# FULLMONI-WIDE_IF-Board1_SCH.net
KiCad netlist of a schematic drawn in EAGLE
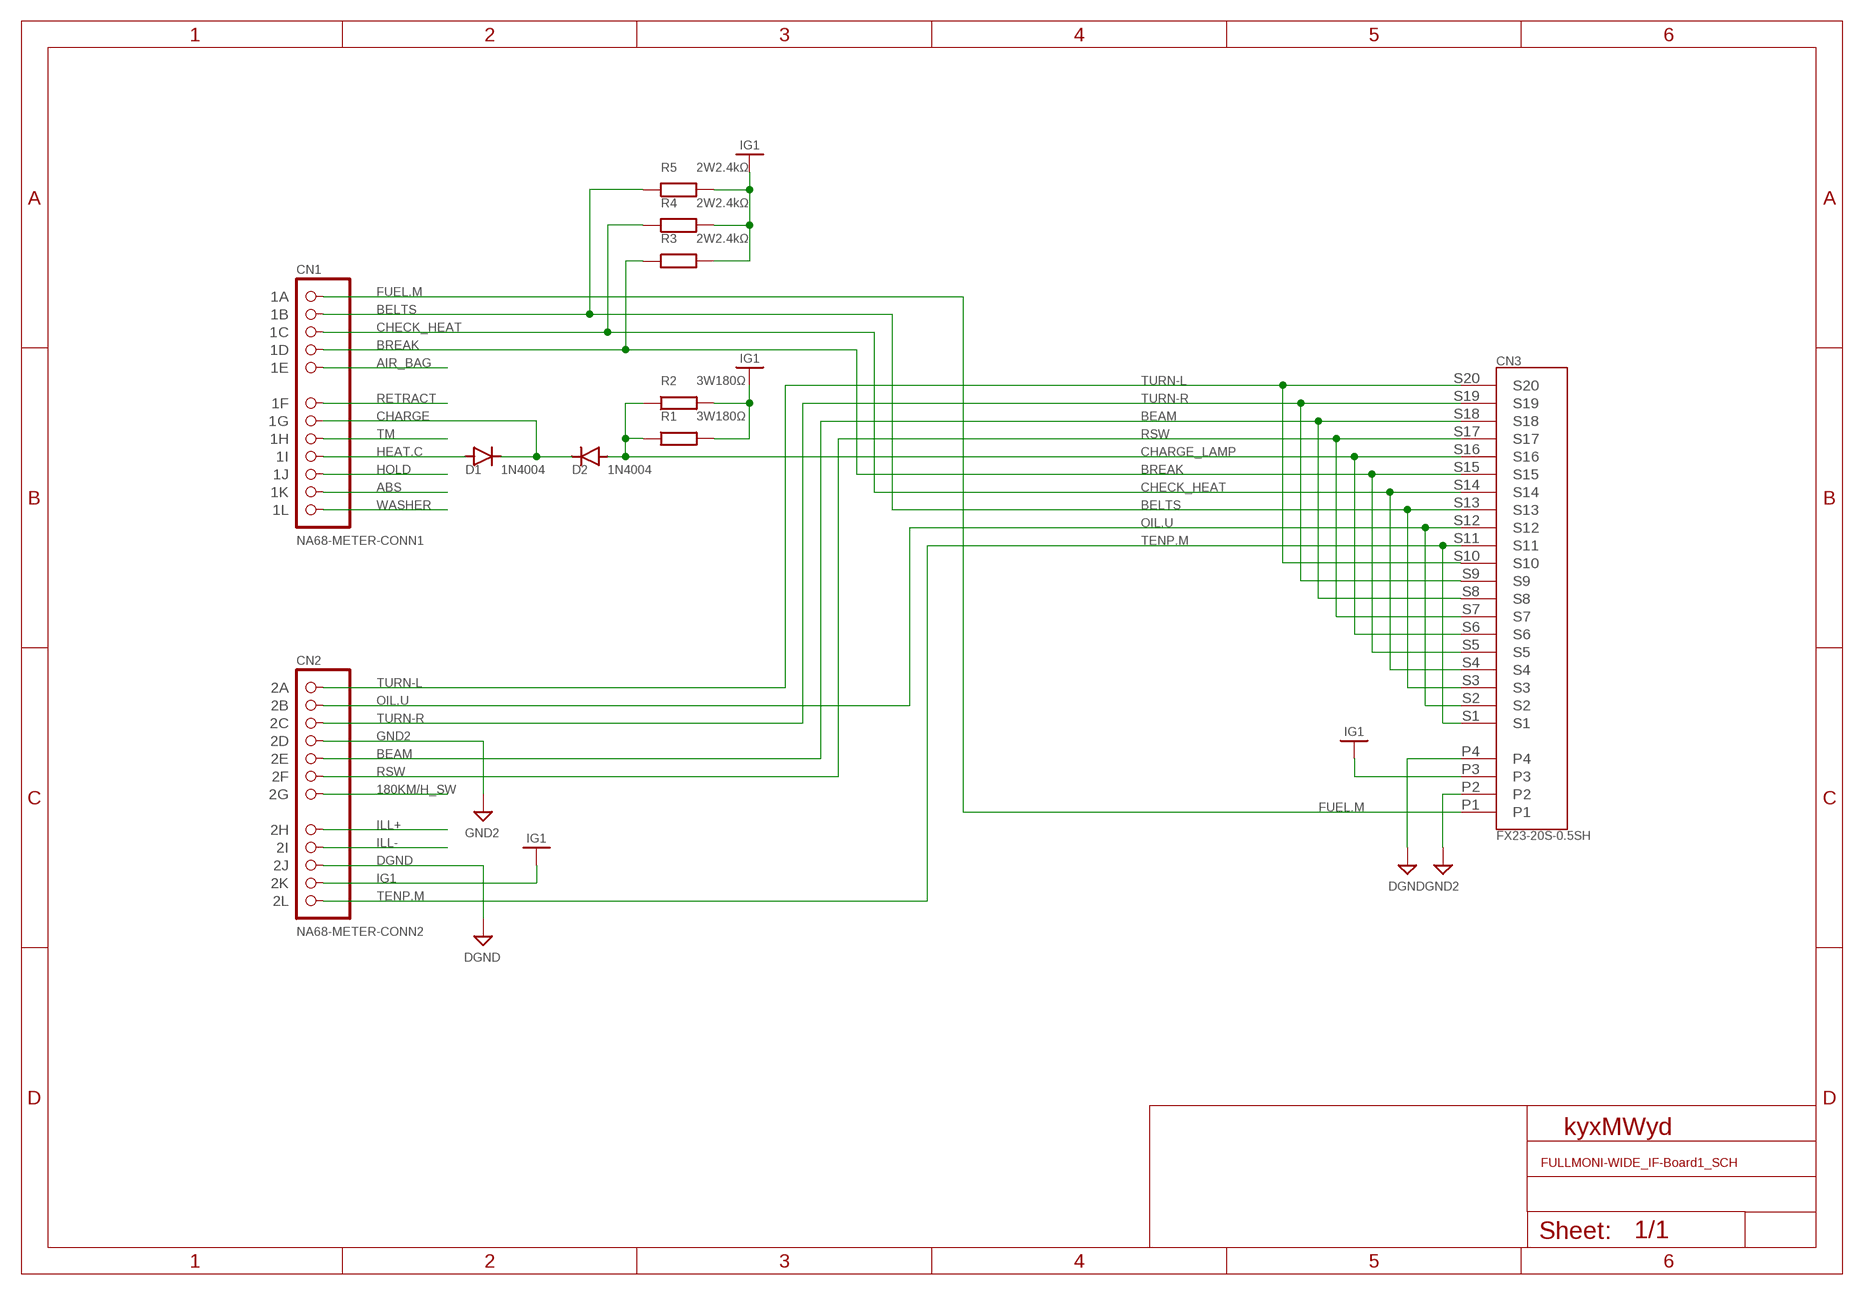
[diagram p0: schematic, sheet 1]

(export (version "E")
  (design (tool "Eeschema 10.0.6"))
  (components
    (comp (ref "CN1")
      (value "NA68-METER-CONN1")
      (footprint "eagle-import:NA68-METER-CONN1")
      (libsource (lib "eagle-import") (part "NA68-METER-CONN1"))
    )
    (comp (ref "CN2")
      (value "NA68-METER-CONN2")
      (footprint "eagle-import:NA68-METER-CONN2")
      (libsource (lib "eagle-import") (part "NA68-METER-CONN2"))
    )
    (comp (ref "CN3")
      (value "FX23-20S-0.5SH")
      (footprint "eagle-import:FX23-20S-0.5SH")
      (libsource (lib "eagle-import") (part "FX23-20S-0.5SH"))
    )
    (comp (ref "D1")
      (value "1N4004")
      (footprint "eagle-import:DO41-10")
      (libsource (lib "eagle-import") (part "1N4004"))
    )
    (comp (ref "D2")
      (value "1N4004")
      (footprint "eagle-import:DO41-10")
      (libsource (lib "eagle-import") (part "1N4004"))
    )
    (comp (ref "R1")
      (value "3W180Ω")
      (footprint "eagle-import:0617_17")
      (libsource (lib "eagle-import") (part "R-EU_0617/17"))
    )
    (comp (ref "R2")
      (value "3W180Ω")
      (footprint "eagle-import:0617_17")
      (libsource (lib "eagle-import") (part "R-EU_0617/17"))
    )
    (comp (ref "R3")
      (value "2W2.4kΩ")
      (footprint "eagle-import:RLF2SJ")
      (libsource (lib "eagle-import") (part "RLF2SJ"))
    )
    (comp (ref "R4")
      (value "2W2.4kΩ")
      (footprint "eagle-import:RLF2SJ")
      (libsource (lib "eagle-import") (part "RLF2SJ"))
    )
    (comp (ref "R5")
      (value "2W2.4kΩ")
      (footprint "eagle-import:RLF2SJ")
      (libsource (lib "eagle-import") (part "RLF2SJ"))
    )
  )
  (nets
    (net (code "1") (name "+V") (class "Default")
      (node (ref "CN2") (pin "P$11") (pinfunction "2K_P$11") (pintype "passive"))
      (node (ref "CN3") (pin "P3") (pinfunction "P3_P3") (pintype "bidirectional"))
      (node (ref "R1") (pin "2") (pinfunction "2_2") (pintype "passive"))
      (node (ref "R2") (pin "2") (pinfunction "2_2") (pintype "passive"))
      (node (ref "R3") (pin "2") (pinfunction "2_2") (pintype "passive"))
      (node (ref "R4") (pin "2") (pinfunction "2_2") (pintype "passive"))
      (node (ref "R5") (pin "2") (pinfunction "2_2") (pintype "passive"))
    )
    (net (code "2") (name "/180KM{slash}H_SW") (class "Default")
      (node (ref "CN2") (pin "P$7") (pinfunction "2G_P$7") (pintype "passive"))
    )
    (net (code "3") (name "/ABS") (class "Default")
      (node (ref "CN1") (pin "P$11") (pinfunction "1K_P$11") (pintype "passive"))
    )
    (net (code "4") (name "/AIR_BAG") (class "Default")
      (node (ref "CN1") (pin "P$5") (pinfunction "1E_P$5") (pintype "passive"))
    )
    (net (code "5") (name "/BEAM") (class "Default")
      (node (ref "CN2") (pin "P$5") (pinfunction "2E_P$5") (pintype "passive"))
      (node (ref "CN3") (pin "S18") (pinfunction "S18_S18") (pintype "bidirectional"))
      (node (ref "CN3") (pin "S8") (pinfunction "S8_S8") (pintype "bidirectional"))
    )
    (net (code "6") (name "/BELTS") (class "Default")
      (node (ref "CN1") (pin "P$2") (pinfunction "1B_P$2") (pintype "passive"))
      (node (ref "CN3") (pin "S13") (pinfunction "S13_S13") (pintype "bidirectional"))
      (node (ref "CN3") (pin "S3") (pinfunction "S3_S3") (pintype "bidirectional"))
      (node (ref "R5") (pin "1") (pinfunction "1_1") (pintype "passive"))
    )
    (net (code "7") (name "/BREAK") (class "Default")
      (node (ref "CN1") (pin "P$4") (pinfunction "1D_P$4") (pintype "passive"))
      (node (ref "CN3") (pin "S15") (pinfunction "S15_S15") (pintype "bidirectional"))
      (node (ref "CN3") (pin "S5") (pinfunction "S5_S5") (pintype "bidirectional"))
      (node (ref "R3") (pin "1") (pinfunction "1_1") (pintype "passive"))
    )
    (net (code "8") (name "/CHARGE") (class "Default")
      (node (ref "CN1") (pin "P$7") (pinfunction "1G_P$7") (pintype "passive"))
      (node (ref "D1") (pin "C") (pinfunction "C_C") (pintype "passive"))
      (node (ref "D2") (pin "C") (pinfunction "C_C") (pintype "passive"))
    )
    (net (code "9") (name "/CHARGE_LAMP") (class "Default")
      (node (ref "CN3") (pin "S16") (pinfunction "S16_S16") (pintype "bidirectional"))
      (node (ref "CN3") (pin "S6") (pinfunction "S6_S6") (pintype "bidirectional"))
      (node (ref "D2") (pin "A") (pinfunction "A_A") (pintype "passive"))
      (node (ref "R1") (pin "1") (pinfunction "1_1") (pintype "passive"))
      (node (ref "R2") (pin "1") (pinfunction "1_1") (pintype "passive"))
    )
    (net (code "10") (name "/CHECK_HEAT") (class "Default")
      (node (ref "CN1") (pin "P$3") (pinfunction "1C_P$3") (pintype "passive"))
      (node (ref "CN3") (pin "S14") (pinfunction "S14_S14") (pintype "bidirectional"))
      (node (ref "CN3") (pin "S4") (pinfunction "S4_S4") (pintype "bidirectional"))
      (node (ref "R4") (pin "1") (pinfunction "1_1") (pintype "passive"))
    )
    (net (code "11") (name "/FUEL.M") (class "Default")
      (node (ref "CN1") (pin "P$1") (pinfunction "1A_P$1") (pintype "passive"))
      (node (ref "CN3") (pin "P1") (pinfunction "P1_P1") (pintype "bidirectional"))
    )
    (net (code "12") (name "/HEAT.C") (class "Default")
      (node (ref "CN1") (pin "P$9") (pinfunction "1I_P$9") (pintype "passive"))
      (node (ref "D1") (pin "A") (pinfunction "A_A") (pintype "passive"))
    )
    (net (code "13") (name "/HOLD") (class "Default")
      (node (ref "CN1") (pin "P$10") (pinfunction "1J_P$10") (pintype "passive"))
    )
    (net (code "14") (name "/ILL+") (class "Default")
      (node (ref "CN2") (pin "P$8") (pinfunction "2H_P$8") (pintype "passive"))
    )
    (net (code "15") (name "/ILL-") (class "Default")
      (node (ref "CN2") (pin "P$9") (pinfunction "2I_P$9") (pintype "passive"))
    )
    (net (code "16") (name "/OIL.U") (class "Default")
      (node (ref "CN2") (pin "P$2") (pinfunction "2B_P$2") (pintype "passive"))
      (node (ref "CN3") (pin "S12") (pinfunction "S12_S12") (pintype "bidirectional"))
      (node (ref "CN3") (pin "S2") (pinfunction "S2_S2") (pintype "bidirectional"))
    )
    (net (code "17") (name "/RETRACT") (class "Default")
      (node (ref "CN1") (pin "P$6") (pinfunction "1F_P$6") (pintype "passive"))
    )
    (net (code "18") (name "/RSW") (class "Default")
      (node (ref "CN2") (pin "P$6") (pinfunction "2F_P$6") (pintype "passive"))
      (node (ref "CN3") (pin "S17") (pinfunction "S17_S17") (pintype "bidirectional"))
      (node (ref "CN3") (pin "S7") (pinfunction "S7_S7") (pintype "bidirectional"))
    )
    (net (code "19") (name "/TENP.M") (class "Default")
      (node (ref "CN2") (pin "P$12") (pinfunction "2L_P$12") (pintype "passive"))
      (node (ref "CN3") (pin "S1") (pinfunction "S1_S1") (pintype "bidirectional"))
      (node (ref "CN3") (pin "S11") (pinfunction "S11_S11") (pintype "bidirectional"))
    )
    (net (code "20") (name "/TM") (class "Default")
      (node (ref "CN1") (pin "P$8") (pinfunction "1H_P$8") (pintype "passive"))
    )
    (net (code "21") (name "/TURN-L") (class "Default")
      (node (ref "CN2") (pin "P$1") (pinfunction "2A_P$1") (pintype "passive"))
      (node (ref "CN3") (pin "S10") (pinfunction "S10_S10") (pintype "bidirectional"))
      (node (ref "CN3") (pin "S20") (pinfunction "S20_S20") (pintype "bidirectional"))
    )
    (net (code "22") (name "/TURN-R") (class "Default")
      (node (ref "CN2") (pin "P$3") (pinfunction "2C_P$3") (pintype "passive"))
      (node (ref "CN3") (pin "S19") (pinfunction "S19_S19") (pintype "bidirectional"))
      (node (ref "CN3") (pin "S9") (pinfunction "S9_S9") (pintype "bidirectional"))
    )
    (net (code "23") (name "/WASHER") (class "Default")
      (node (ref "CN1") (pin "P$12") (pinfunction "1L_P$12") (pintype "passive"))
    )
    (net (code "24") (name "DGND") (class "Default")
      (node (ref "CN2") (pin "P$10") (pinfunction "2J_P$10") (pintype "passive"))
      (node (ref "CN3") (pin "P4") (pinfunction "P4_P4") (pintype "bidirectional"))
    )
    (net (code "25") (name "GND2") (class "Default")
      (node (ref "CN2") (pin "P$4") (pinfunction "2D_P$4") (pintype "passive"))
      (node (ref "CN3") (pin "P2") (pinfunction "P2_P2") (pintype "bidirectional"))
    )
  )
)
